# Schema.net
KiCad netlist of a schematic drawn in Altium Designer
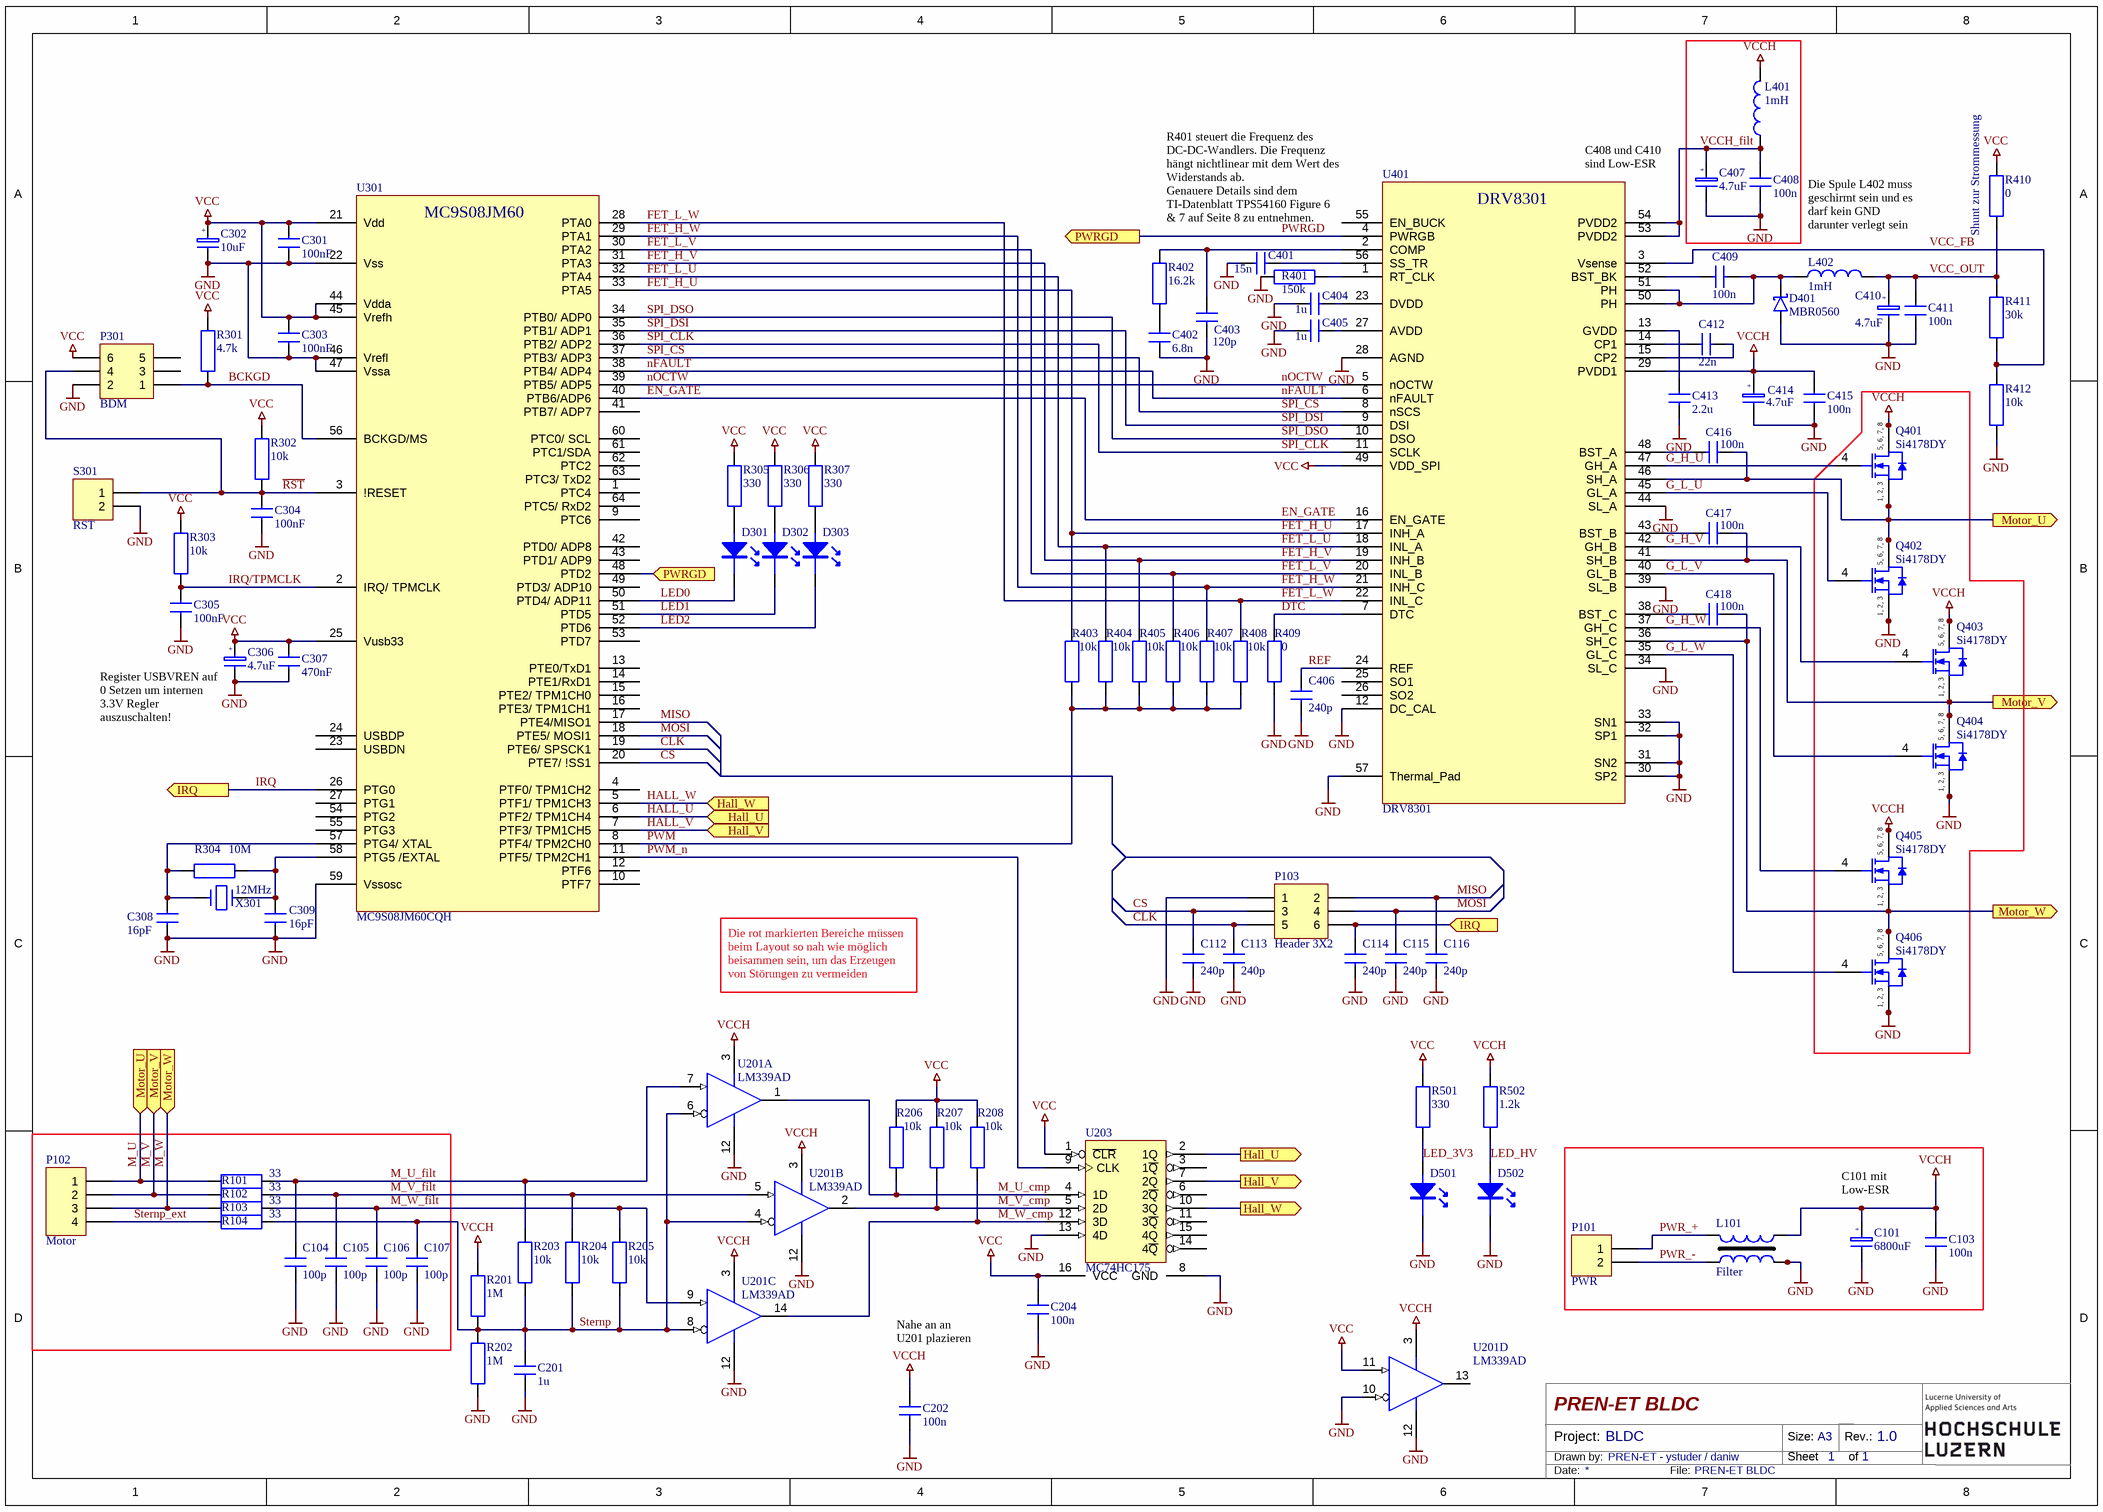
[diagram p0: Schema.SchDoc]

(export (version "E")
  (design (tool "Eeschema 10.0.6"))
  (components
    (comp (ref "C101")
      (value "6800uF")
      (footprint "CAPPA14.05-10.5x6.3")
      (description "Elektrolyt /polarisierter Kondensator")
      (libsource (lib "BLDC_Board_Library") (part "C? ELKO"))
    )
    (comp (ref "C103")
      (value "100n")
      (footprint "0805")
      (description "Normaler Kondensator")
      (libsource (lib "SPICE_HSLU") (part "C?"))
    )
    (comp (ref "C104")
      (value "100p")
      (footprint "0805")
      (description "Normaler Kondensator")
      (libsource (lib "SPICE_HSLU") (part "C?"))
    )
    (comp (ref "C105")
      (value "100p")
      (footprint "0805")
      (description "Normaler Kondensator")
      (libsource (lib "SPICE_HSLU") (part "C?"))
    )
    (comp (ref "C106")
      (value "100p")
      (footprint "0805")
      (description "Normaler Kondensator")
      (libsource (lib "SPICE_HSLU") (part "C?"))
    )
    (comp (ref "C107")
      (value "100p")
      (footprint "0805")
      (description "Normaler Kondensator")
      (libsource (lib "SPICE_HSLU") (part "C?"))
    )
    (comp (ref "C112")
      (value "240p")
      (footprint "0805")
      (description "Normaler Kondensator")
      (libsource (lib "SPICE_HSLU") (part "C?"))
    )
    (comp (ref "C113")
      (value "240p")
      (footprint "0805")
      (description "Normaler Kondensator")
      (libsource (lib "SPICE_HSLU") (part "C?"))
    )
    (comp (ref "C114")
      (value "240p")
      (footprint "0805")
      (description "Normaler Kondensator")
      (libsource (lib "SPICE_HSLU") (part "C?"))
    )
    (comp (ref "C115")
      (value "240p")
      (footprint "0805")
      (description "Normaler Kondensator")
      (libsource (lib "SPICE_HSLU") (part "C?"))
    )
    (comp (ref "C116")
      (value "240p")
      (footprint "0805")
      (description "Normaler Kondensator")
      (libsource (lib "SPICE_HSLU") (part "C?"))
    )
    (comp (ref "C201")
      (value "1u")
      (footprint "0805")
      (description "Normaler Kondensator")
      (libsource (lib "SPICE_HSLU") (part "C?"))
    )
    (comp (ref "C202")
      (value "100n")
      (footprint "0805")
      (description "Normaler Kondensator")
      (libsource (lib "SPICE_HSLU") (part "C?"))
    )
    (comp (ref "C204")
      (value "100n")
      (footprint "0805")
      (description "Normaler Kondensator")
      (libsource (lib "SPICE_HSLU") (part "C?"))
    )
    (comp (ref "C301")
      (value "100nF")
      (footprint "0805")
      (description "Normaler Kondensator")
      (libsource (lib "DEVICE_HSLU") (part "C?"))
    )
    (comp (ref "C302")
      (value "10uF")
      (footprint "1206")
      (description "Elektrolyt /polarisierter Kondensator")
      (libsource (lib "BLDC_Board_Library") (part "C? ELKO"))
    )
    (comp (ref "C303")
      (value "100nF")
      (footprint "0805")
      (description "Normaler Kondensator")
      (libsource (lib "DEVICE_HSLU") (part "C?"))
    )
    (comp (ref "C304")
      (value "100nF")
      (footprint "0805")
      (description "Normaler Kondensator")
      (libsource (lib "DEVICE_HSLU") (part "C?"))
    )
    (comp (ref "C305")
      (value "100nF")
      (footprint "0805")
      (description "Normaler Kondensator")
      (libsource (lib "DEVICE_HSLU") (part "C?"))
    )
    (comp (ref "C306")
      (value "4.7uF")
      (footprint "1206")
      (description "Elektrolyt /polarisierter Kondensator")
      (libsource (lib "BLDC_Board_Library") (part "C? ELKO"))
    )
    (comp (ref "C307")
      (value "470nF")
      (footprint "0805")
      (description "Normaler Kondensator")
      (libsource (lib "PREN_Demoboard") (part "C?"))
    )
    (comp (ref "C308")
      (value "16pF")
      (footprint "0805")
      (description "Normaler Kondensator")
      (libsource (lib "DEVICE_HSLU") (part "C?"))
    )
    (comp (ref "C309")
      (value "16pF")
      (footprint "0805")
      (description "Normaler Kondensator")
      (libsource (lib "DEVICE_HSLU") (part "C?"))
    )
    (comp (ref "C401")
      (value "15n")
      (footprint "0805")
      (description "Normaler Kondensator")
      (libsource (lib "SPICE_HSLU") (part "C?"))
    )
    (comp (ref "C402")
      (value "6.8n")
      (footprint "0805")
      (description "Normaler Kondensator")
      (libsource (lib "SPICE_HSLU") (part "C?"))
    )
    (comp (ref "C403")
      (value "120p")
      (footprint "0805")
      (description "Normaler Kondensator")
      (libsource (lib "SPICE_HSLU") (part "C?"))
    )
    (comp (ref "C404")
      (value "1u")
      (footprint "0805")
      (description "Normaler Kondensator")
      (libsource (lib "SPICE_HSLU") (part "C?"))
    )
    (comp (ref "C405")
      (value "1u")
      (footprint "0805")
      (description "Normaler Kondensator")
      (libsource (lib "SPICE_HSLU") (part "C?"))
    )
    (comp (ref "C406")
      (value "240p")
      (footprint "0805")
      (description "Normaler Kondensator")
      (libsource (lib "SPICE_HSLU") (part "C?"))
    )
    (comp (ref "C407")
      (value "4.7uF")
      (footprint "1206")
      (description "Elektrolyt /polarisierter Kondensator")
      (libsource (lib "BLDC_Board_Library") (part "C? ELKO"))
    )
    (comp (ref "C408")
      (value "100n")
      (footprint "0805")
      (description "Normaler Kondensator")
      (libsource (lib "SPICE_HSLU") (part "C?"))
    )
    (comp (ref "C409")
      (value "100n")
      (footprint "0805")
      (description "Normaler Kondensator")
      (libsource (lib "SPICE_HSLU") (part "C?"))
    )
    (comp (ref "C410")
      (value "4.7uF")
      (footprint "1206")
      (description "Elektrolyt /polarisierter Kondensator")
      (libsource (lib "BLDC_Board_Library") (part "C? ELKO"))
    )
    (comp (ref "C411")
      (value "100n")
      (footprint "0805")
      (description "Normaler Kondensator")
      (libsource (lib "SPICE_HSLU") (part "C?"))
    )
    (comp (ref "C412")
      (value "22n")
      (footprint "0805")
      (description "Normaler Kondensator")
      (libsource (lib "SPICE_HSLU") (part "C?"))
    )
    (comp (ref "C413")
      (value "2.2u")
      (footprint "0805")
      (description "Normaler Kondensator")
      (libsource (lib "SPICE_HSLU") (part "C?"))
    )
    (comp (ref "C414")
      (value "4.7uF")
      (footprint "1206")
      (description "Elektrolyt /polarisierter Kondensator")
      (libsource (lib "BLDC_Board_Library") (part "C? ELKO"))
    )
    (comp (ref "C415")
      (value "100n")
      (footprint "0805")
      (description "Normaler Kondensator")
      (libsource (lib "SPICE_HSLU") (part "C?"))
    )
    (comp (ref "C416")
      (value "100n")
      (footprint "0805")
      (description "Normaler Kondensator")
      (libsource (lib "SPICE_HSLU") (part "C?"))
    )
    (comp (ref "C417")
      (value "100n")
      (footprint "0805")
      (description "Normaler Kondensator")
      (libsource (lib "SPICE_HSLU") (part "C?"))
    )
    (comp (ref "C418")
      (value "100n")
      (footprint "0805")
      (description "Normaler Kondensator")
      (libsource (lib "SPICE_HSLU") (part "C?"))
    )
    (comp (ref "D301") (value "LED") (footprint "0805") (libsource (lib "BLDC_Board_Library") (part "LED")))
    (comp (ref "D302") (value "LED") (footprint "0805") (libsource (lib "BLDC_Board_Library") (part "LED")))
    (comp (ref "D303") (value "LED") (footprint "0805") (libsource (lib "BLDC_Board_Library") (part "LED")))
    (comp (ref "D401")
      (value "MBR0560")
      (footprint "SOD-123")
      (description "Schottky Diode")
      (libsource (lib "BLDC_Board_Library") (part "DiodeSchottky"))
    )
    (comp (ref "D501") (value "LED") (footprint "0805") (libsource (lib "BLDC_Board_Library") (part "LED")))
    (comp (ref "D502") (value "LED") (footprint "0805") (libsource (lib "BLDC_Board_Library") (part "LED")))
    (comp (ref "L101")
      (value "Filter")
      (footprint "BNX")
      (libsource (lib "BLDC_Board_Library") (part "CommonFilter"))
    )
    (comp (ref "L401")
      (value "1mH")
      (footprint "SRR6603")
      (description "SRR1005-122K")
      (libsource (lib "SPICE_HSLU") (part "L?"))
    )
    (comp (ref "L402")
      (value "1mH")
      (footprint "SRR6603")
      (description "SRR1005-122K")
      (libsource (lib "SPICE_HSLU") (part "L?"))
    )
    (comp (ref "P101")
      (value "PWR")
      (footprint "Stecker_1x2_200mil")
      (description "Header, 2-Pin")
      (fields (field (name "PUBLISHER") "Altium Limited"))
      (libsource (lib "BLDC_Board_Library") (part "Header 2"))
    )
    (comp (ref "P102")
      (value "Motor")
      (footprint "Stecker_1x4_200mil")
      (description "Header, 4-Pin")
      (fields (field (name "PUBLISHER") "Altium Limited"))
      (libsource (lib "BLDC_Board_Library") (part "Header 4"))
    )
    (comp (ref "P103")
      (value "Header 3X2")
      (footprint "HDR2X3")
      (description "Header, 3-Pin, Dual row")
      (fields (field (name "PUBLISHER") "Altium Limited"))
      (libsource (lib "Miscellaneous Connectors") (part "Header 3X2"))
    )
    (comp (ref "P301")
      (value "BDM")
      (footprint "HDR2X3")
      (description "Header, 3-Pin, Dual row")
      (libsource (lib "") (part "Header 3X2_1"))
    )
    (comp (ref "Q401")
      (value "Si4178DY")
      (footprint "SO-8_N")
      (description "N-Channel 30V (D-S)  Rated MOSFET")
      (fields (field (name "PUBLISHER") "Altium Limited"))
      (libsource (lib "Vishay Siliconix Discrete MOSFET") (part "SI4412DY"))
    )
    (comp (ref "Q402")
      (value "Si4178DY")
      (footprint "SO-8_N")
      (description "N-Channel 30V (D-S)  Rated MOSFET")
      (fields (field (name "PUBLISHER") "Altium Limited"))
      (libsource (lib "Vishay Siliconix Discrete MOSFET") (part "SI4412DY"))
    )
    (comp (ref "Q403")
      (value "Si4178DY")
      (footprint "SO-8_N")
      (description "N-Channel 30V (D-S)  Rated MOSFET")
      (fields (field (name "PUBLISHER") "Altium Limited"))
      (libsource (lib "Vishay Siliconix Discrete MOSFET") (part "SI4412DY"))
    )
    (comp (ref "Q404")
      (value "Si4178DY")
      (footprint "SO-8_N")
      (description "N-Channel 30V (D-S)  Rated MOSFET")
      (fields (field (name "PUBLISHER") "Altium Limited"))
      (libsource (lib "Vishay Siliconix Discrete MOSFET") (part "SI4412DY"))
    )
    (comp (ref "Q405")
      (value "Si4178DY")
      (footprint "SO-8_N")
      (description "N-Channel 30V (D-S)  Rated MOSFET")
      (fields (field (name "PUBLISHER") "Altium Limited"))
      (libsource (lib "Vishay Siliconix Discrete MOSFET") (part "SI4412DY"))
    )
    (comp (ref "Q406")
      (value "Si4178DY")
      (footprint "SO-8_N")
      (description "N-Channel 30V (D-S)  Rated MOSFET")
      (fields (field (name "PUBLISHER") "Altium Limited"))
      (libsource (lib "Vishay Siliconix Discrete MOSFET") (part "SI4412DY"))
    )
    (comp (ref "R101")
      (value "33")
      (footprint "0805")
      (description "Normaler Widerstand")
      (libsource (lib "SPICE_HSLU") (part "R?"))
    )
    (comp (ref "R102")
      (value "33")
      (footprint "0805")
      (description "Normaler Widerstand")
      (libsource (lib "SPICE_HSLU") (part "R?"))
    )
    (comp (ref "R103")
      (value "33")
      (footprint "0805")
      (description "Normaler Widerstand")
      (libsource (lib "SPICE_HSLU") (part "R?"))
    )
    (comp (ref "R104")
      (value "33")
      (footprint "0805")
      (description "Normaler Widerstand")
      (libsource (lib "SPICE_HSLU") (part "R?"))
    )
    (comp (ref "R201")
      (value "1M")
      (footprint "0805")
      (description "Normaler Widerstand")
      (libsource (lib "SPICE_HSLU") (part "R?"))
    )
    (comp (ref "R202")
      (value "1M")
      (footprint "0805")
      (description "Normaler Widerstand")
      (libsource (lib "SPICE_HSLU") (part "R?"))
    )
    (comp (ref "R203")
      (value "10k")
      (footprint "0805")
      (description "Normaler Widerstand")
      (libsource (lib "SPICE_HSLU") (part "R?"))
    )
    (comp (ref "R204")
      (value "10k")
      (footprint "0805")
      (description "Normaler Widerstand")
      (libsource (lib "SPICE_HSLU") (part "R?"))
    )
    (comp (ref "R205")
      (value "10k")
      (footprint "0805")
      (description "Normaler Widerstand")
      (libsource (lib "SPICE_HSLU") (part "R?"))
    )
    (comp (ref "R206")
      (value "10k")
      (footprint "0805")
      (description "Normaler Widerstand")
      (libsource (lib "SPICE_HSLU") (part "R?"))
    )
    (comp (ref "R207")
      (value "10k")
      (footprint "0805")
      (description "Normaler Widerstand")
      (libsource (lib "SPICE_HSLU") (part "R?"))
    )
    (comp (ref "R208")
      (value "10k")
      (footprint "0805")
      (description "Normaler Widerstand")
      (libsource (lib "SPICE_HSLU") (part "R?"))
    )
    (comp (ref "R301")
      (value "4.7k")
      (footprint "0805")
      (description "Normaler Widerstand")
      (libsource (lib "DEVICE_HSLU") (part "R?"))
    )
    (comp (ref "R302")
      (value "10k")
      (footprint "0805")
      (description "Normaler Widerstand")
      (libsource (lib "DEVICE_HSLU") (part "R?"))
    )
    (comp (ref "R303")
      (value "10k")
      (footprint "0805")
      (description "Normaler Widerstand")
      (libsource (lib "DEVICE_HSLU") (part "R?"))
    )
    (comp (ref "R304")
      (value "10M")
      (footprint "0805")
      (description "Normaler Widerstand")
      (libsource (lib "DEVICE_HSLU") (part "R?"))
    )
    (comp (ref "R305")
      (value "330")
      (footprint "0805")
      (description "Normaler Widerstand")
      (libsource (lib "SPICE_HSLU") (part "R?"))
    )
    (comp (ref "R306")
      (value "330")
      (footprint "0805")
      (description "Normaler Widerstand")
      (libsource (lib "SPICE_HSLU") (part "R?"))
    )
    (comp (ref "R307")
      (value "330")
      (footprint "0805")
      (description "Normaler Widerstand")
      (libsource (lib "SPICE_HSLU") (part "R?"))
    )
    (comp (ref "R401")
      (value "150k")
      (footprint "0805")
      (description "Normaler Widerstand")
      (libsource (lib "SPICE_HSLU") (part "R?"))
    )
    (comp (ref "R402")
      (value "16.2k")
      (footprint "0805")
      (description "Normaler Widerstand")
      (libsource (lib "SPICE_HSLU") (part "R?"))
    )
    (comp (ref "R403")
      (value "10k")
      (footprint "0805")
      (description "Normaler Widerstand")
      (libsource (lib "SPICE_HSLU") (part "R?"))
    )
    (comp (ref "R404")
      (value "10k")
      (footprint "0805")
      (description "Normaler Widerstand")
      (libsource (lib "SPICE_HSLU") (part "R?"))
    )
    (comp (ref "R405")
      (value "10k")
      (footprint "0805")
      (description "Normaler Widerstand")
      (libsource (lib "SPICE_HSLU") (part "R?"))
    )
    (comp (ref "R406")
      (value "10k")
      (footprint "0805")
      (description "Normaler Widerstand")
      (libsource (lib "SPICE_HSLU") (part "R?"))
    )
    (comp (ref "R407")
      (value "10k")
      (footprint "0805")
      (description "Normaler Widerstand")
      (libsource (lib "SPICE_HSLU") (part "R?"))
    )
    (comp (ref "R408")
      (value "10k")
      (footprint "0805")
      (description "Normaler Widerstand")
      (libsource (lib "SPICE_HSLU") (part "R?"))
    )
    (comp (ref "R409")
      (value "0")
      (footprint "0805")
      (description "Normaler Widerstand")
      (libsource (lib "SPICE_HSLU") (part "R?"))
    )
    (comp (ref "R410")
      (value "0")
      (footprint "0805")
      (description "Normaler Widerstand")
      (libsource (lib "SPICE_HSLU") (part "R?"))
    )
    (comp (ref "R411")
      (value "30k")
      (footprint "0805")
      (description "Normaler Widerstand")
      (libsource (lib "SPICE_HSLU") (part "R?"))
    )
    (comp (ref "R412")
      (value "10k")
      (footprint "0805")
      (description "Normaler Widerstand")
      (libsource (lib "SPICE_HSLU") (part "R?"))
    )
    (comp (ref "R501")
      (value "330")
      (footprint "0805")
      (description "Normaler Widerstand")
      (libsource (lib "SPICE_HSLU") (part "R?"))
    )
    (comp (ref "R502")
      (value "1.2k")
      (footprint "0805")
      (description "Normaler Widerstand")
      (libsource (lib "SPICE_HSLU") (part "R?"))
    )
    (comp (ref "S301")
      (value "RST")
      (footprint "HDR1X2")
      (description "Header, 2-Pin")
      (fields (field (name "PUBLISHER") "Altium Limited"))
      (libsource (lib "Miscellaneous Connectors") (part "Header 2"))
    )
    (comp (ref "U201")
      (value "LM339AD")
      (footprint "D014_L")
      (description "Quad Differential Comparator")
      (fields (field (name "PUBLISHER") "Altium Limited"))
      (libsource (lib "TI Analog Comparator") (part "LM339AD"))
    )
    (comp (ref "U203")
      (value "MC74HC175")
      (footprint "SO-16")
      (description "QUAD D-TYPE FF CR")
      (libsource (lib "Standardlogik") (part "MC74HC175"))
    )
    (comp (ref "U301")
      (value "MC9S08JM60CQH")
      (footprint "QFP64(14x14)")
      (description "MCU")
      (libsource (lib "PREN_Demoboard") (part "MC9S08JM60"))
    )
    (comp (ref "U401")
      (value "DRV8301")
      (footprint "HTSSOP56")
      (libsource (lib "BLDC_Board_Library") (part "DRV8301"))
    )
    (comp (ref "X301") (value "12MHz") (footprint "HC/49US") (libsource (lib "DEVICE_HSLU") (part "CRYSTAL")))
  )
  (nets
    (net (code "1") (name "/BCKGD") (class "Default")
      (node (ref "P301") (pin "1") (pinfunction "1_1") (pintype "passive"))
      (node (ref "R301") (pin "2") (pintype "passive"))
      (node (ref "U301") (pin "56") (pinfunction "BCKGD/MS_56") (pintype "passive"))
    )
    (net (code "2") (name "/CLK") (class "Default")
      (node (ref "C113") (pin "1") (pinfunction "1_1") (pintype "passive"))
      (node (ref "P103") (pin "5") (pinfunction "5_5") (pintype "passive"))
      (node (ref "U301") (pin "19") (pinfunction "PTE6/_SPSCK1_19") (pintype "passive"))
    )
    (net (code "3") (name "/CS") (class "Default")
      (node (ref "C112") (pin "1") (pinfunction "1_1") (pintype "passive"))
      (node (ref "P103") (pin "3") (pinfunction "3_3") (pintype "passive"))
      (node (ref "U301") (pin "20") (pinfunction "PTE7/_!SS1_20") (pintype "passive"))
    )
    (net (code "4") (name "/DTC") (class "Default")
      (node (ref "R409") (pin "2") (pintype "passive"))
      (node (ref "U401") (pin "7") (pinfunction "DTC_7") (pintype "passive"))
    )
    (net (code "5") (name "/EN_GATE") (class "Default")
      (node (ref "U301") (pin "40") (pinfunction "PTB6/ADP6_40") (pintype "passive"))
      (node (ref "U401") (pin "16") (pinfunction "EN_GATE_16") (pintype "passive"))
    )
    (net (code "6") (name "/FET_H_U") (class "Default")
      (node (ref "R403") (pin "2") (pintype "passive"))
      (node (ref "U301") (pin "33") (pinfunction "PTA5_33") (pintype "passive"))
      (node (ref "U401") (pin "17") (pinfunction "INH_A_17") (pintype "passive"))
    )
    (net (code "7") (name "/FET_H_V") (class "Default")
      (node (ref "R405") (pin "2") (pintype "passive"))
      (node (ref "U301") (pin "31") (pinfunction "PTA3_31") (pintype "passive"))
      (node (ref "U401") (pin "19") (pinfunction "INH_B_19") (pintype "passive"))
    )
    (net (code "8") (name "/FET_H_W") (class "Default")
      (node (ref "R407") (pin "2") (pintype "passive"))
      (node (ref "U301") (pin "29") (pinfunction "PTA1_29") (pintype "passive"))
      (node (ref "U401") (pin "21") (pinfunction "INH_C_21") (pintype "passive"))
    )
    (net (code "9") (name "/FET_L_U") (class "Default")
      (node (ref "R404") (pin "2") (pintype "passive"))
      (node (ref "U301") (pin "32") (pinfunction "PTA4_32") (pintype "passive"))
      (node (ref "U401") (pin "18") (pinfunction "INL_A_18") (pintype "passive"))
    )
    (net (code "10") (name "/FET_L_V") (class "Default")
      (node (ref "R406") (pin "2") (pintype "passive"))
      (node (ref "U301") (pin "30") (pinfunction "PTA2_30") (pintype "passive"))
      (node (ref "U401") (pin "20") (pinfunction "INL_B_20") (pintype "passive"))
    )
    (net (code "11") (name "/FET_L_W") (class "Default")
      (node (ref "R408") (pin "2") (pintype "passive"))
      (node (ref "U301") (pin "28") (pinfunction "PTA0_28") (pintype "passive"))
      (node (ref "U401") (pin "22") (pinfunction "INL_C_22") (pintype "passive"))
    )
    (net (code "12") (name "/G_H_U") (class "Default")
      (node (ref "Q401") (pin "4") (pinfunction "G_4") (pintype "passive"))
      (node (ref "U401") (pin "47") (pinfunction "GH_A_47") (pintype "passive"))
    )
    (net (code "13") (name "/G_H_V") (class "Default")
      (node (ref "Q403") (pin "4") (pinfunction "G_4") (pintype "passive"))
      (node (ref "U401") (pin "42") (pinfunction "GH_B_42") (pintype "passive"))
    )
    (net (code "14") (name "/G_H_W") (class "Default")
      (node (ref "Q405") (pin "4") (pinfunction "G_4") (pintype "passive"))
      (node (ref "U401") (pin "37") (pinfunction "GH_C_37") (pintype "passive"))
    )
    (net (code "15") (name "/G_L_U") (class "Default")
      (node (ref "Q402") (pin "4") (pinfunction "G_4") (pintype "passive"))
      (node (ref "U401") (pin "45") (pinfunction "GL_A_45") (pintype "passive"))
    )
    (net (code "16") (name "/G_L_V") (class "Default")
      (node (ref "Q404") (pin "4") (pinfunction "G_4") (pintype "passive"))
      (node (ref "U401") (pin "40") (pinfunction "GL_B_40") (pintype "passive"))
    )
    (net (code "17") (name "/G_L_W") (class "Default")
      (node (ref "Q406") (pin "4") (pinfunction "G_4") (pintype "passive"))
      (node (ref "U401") (pin "35") (pinfunction "GL_C_35") (pintype "passive"))
    )
    (net (code "18") (name "/HALL_U") (class "Default")
      (node (ref "U203") (pin "2") (pinfunction "1Q_2") (pintype "output"))
      (node (ref "U301") (pin "6") (pinfunction "PTF2/_TPM1CH4_6") (pintype "passive"))
    )
    (net (code "19") (name "/HALL_V") (class "Default")
      (node (ref "U203") (pin "7") (pinfunction "2Q_7") (pintype "output"))
      (node (ref "U301") (pin "7") (pinfunction "PTF3/_TPM1CH5_7") (pintype "passive"))
    )
    (net (code "20") (name "/HALL_W") (class "Default")
      (node (ref "U203") (pin "10") (pinfunction "3Q_10") (pintype "output"))
      (node (ref "U301") (pin "5") (pinfunction "PTF1/_TPM1CH3_5") (pintype "passive"))
    )
    (net (code "21") (name "/IRQ") (class "Default")
      (node (ref "C114") (pin "1") (pinfunction "1_1") (pintype "passive"))
      (node (ref "P103") (pin "6") (pinfunction "6_6") (pintype "passive"))
      (node (ref "U301") (pin "26") (pinfunction "PTG0_26") (pintype "passive"))
    )
    (net (code "22") (name "/IRQ{slash}TPMCLK") (class "Default")
      (node (ref "C305") (pin "1") (pinfunction "1_1") (pintype "passive"))
      (node (ref "R303") (pin "2") (pintype "passive"))
      (node (ref "U301") (pin "2") (pinfunction "IRQ/_TPMCLK_2") (pintype "passive"))
    )
    (net (code "23") (name "/LED0") (class "Default")
      (node (ref "D301") (pin "1") (pintype "passive"))
      (node (ref "U301") (pin "50") (pinfunction "PTD4/_ADP11_50") (pintype "passive"))
    )
    (net (code "24") (name "/LED1") (class "Default")
      (node (ref "D302") (pin "1") (pintype "passive"))
      (node (ref "U301") (pin "51") (pinfunction "PTD5_51") (pintype "passive"))
    )
    (net (code "25") (name "/LED2") (class "Default")
      (node (ref "D303") (pin "1") (pintype "passive"))
      (node (ref "U301") (pin "52") (pinfunction "PTD6_52") (pintype "passive"))
    )
    (net (code "26") (name "/LED_3V3") (class "Default")
      (node (ref "D501") (pin "2") (pintype "passive"))
      (node (ref "R501") (pin "1") (pintype "passive"))
    )
    (net (code "27") (name "/LED_HV") (class "Default")
      (node (ref "D502") (pin "2") (pintype "passive"))
      (node (ref "R502") (pin "1") (pintype "passive"))
    )
    (net (code "28") (name "/MISO") (class "Default")
      (node (ref "C116") (pin "1") (pinfunction "1_1") (pintype "passive"))
      (node (ref "P103") (pin "2") (pinfunction "2_2") (pintype "passive"))
      (node (ref "U301") (pin "17") (pinfunction "PTE4/MISO1_17") (pintype "passive"))
    )
    (net (code "29") (name "/MOSI") (class "Default")
      (node (ref "C115") (pin "1") (pinfunction "1_1") (pintype "passive"))
      (node (ref "P103") (pin "4") (pinfunction "4_4") (pintype "passive"))
      (node (ref "U301") (pin "18") (pinfunction "PTE5/_MOSI1_18") (pintype "passive"))
    )
    (net (code "30") (name "/M_U") (class "Default")
      (node (ref "C416") (pin "1") (pinfunction "1_1") (pintype "passive"))
      (node (ref "P102") (pin "1") (pinfunction "1_1") (pintype "passive"))
      (node (ref "Q401") (pin "1") (pinfunction "S_1") (pintype "passive"))
      (node (ref "Q401") (pin "2") (pinfunction "S_2") (pintype "passive"))
      (node (ref "Q401") (pin "3") (pinfunction "S_3") (pintype "passive"))
      (node (ref "Q402") (pin "5") (pinfunction "D_5") (pintype "passive"))
      (node (ref "Q402") (pin "6") (pinfunction "D_6") (pintype "passive"))
      (node (ref "Q402") (pin "7") (pinfunction "D_7") (pintype "passive"))
      (node (ref "Q402") (pin "8") (pinfunction "D_8") (pintype "passive"))
      (node (ref "R101") (pin "1") (pintype "passive"))
      (node (ref "U401") (pin "46") (pinfunction "SH_A_46") (pintype "passive"))
    )
    (net (code "31") (name "/M_U_cmp") (class "Default")
      (node (ref "R206") (pin "1") (pintype "passive"))
      (node (ref "U201") (pin "1") (pinfunction "OUT_1") (pintype "open_collector"))
      (node (ref "U203") (pin "4") (pinfunction "1D_4") (pintype "input"))
    )
    (net (code "32") (name "/M_U_filt") (class "Default")
      (node (ref "C104") (pin "1") (pinfunction "1_1") (pintype "passive"))
      (node (ref "R101") (pin "2") (pintype "passive"))
      (node (ref "R203") (pin "2") (pintype "passive"))
      (node (ref "U201") (pin "7") (pinfunction "IN+_7") (pintype "input"))
    )
    (net (code "33") (name "/M_V") (class "Default")
      (node (ref "C417") (pin "1") (pinfunction "1_1") (pintype "passive"))
      (node (ref "P102") (pin "2") (pinfunction "2_2") (pintype "passive"))
      (node (ref "Q403") (pin "1") (pinfunction "S_1") (pintype "passive"))
      (node (ref "Q403") (pin "2") (pinfunction "S_2") (pintype "passive"))
      (node (ref "Q403") (pin "3") (pinfunction "S_3") (pintype "passive"))
      (node (ref "Q404") (pin "5") (pinfunction "D_5") (pintype "passive"))
      (node (ref "Q404") (pin "6") (pinfunction "D_6") (pintype "passive"))
      (node (ref "Q404") (pin "7") (pinfunction "D_7") (pintype "passive"))
      (node (ref "Q404") (pin "8") (pinfunction "D_8") (pintype "passive"))
      (node (ref "R102") (pin "1") (pintype "passive"))
      (node (ref "U401") (pin "41") (pinfunction "SH_B_41") (pintype "passive"))
    )
    (net (code "34") (name "/M_V_cmp") (class "Default")
      (node (ref "R207") (pin "1") (pintype "passive"))
      (node (ref "U201") (pin "2") (pinfunction "OUT_2") (pintype "open_collector"))
      (node (ref "U203") (pin "5") (pinfunction "2D_5") (pintype "input"))
    )
    (net (code "35") (name "/M_V_filt") (class "Default")
      (node (ref "C105") (pin "1") (pinfunction "1_1") (pintype "passive"))
      (node (ref "R102") (pin "2") (pintype "passive"))
      (node (ref "R204") (pin "2") (pintype "passive"))
      (node (ref "U201") (pin "5") (pinfunction "IN+_5") (pintype "input"))
    )
    (net (code "36") (name "/M_W") (class "Default")
      (node (ref "C418") (pin "1") (pinfunction "1_1") (pintype "passive"))
      (node (ref "P102") (pin "3") (pinfunction "3_3") (pintype "passive"))
      (node (ref "Q405") (pin "1") (pinfunction "S_1") (pintype "passive"))
      (node (ref "Q405") (pin "2") (pinfunction "S_2") (pintype "passive"))
      (node (ref "Q405") (pin "3") (pinfunction "S_3") (pintype "passive"))
      (node (ref "Q406") (pin "5") (pinfunction "D_5") (pintype "passive"))
      (node (ref "Q406") (pin "6") (pinfunction "D_6") (pintype "passive"))
      (node (ref "Q406") (pin "7") (pinfunction "D_7") (pintype "passive"))
      (node (ref "Q406") (pin "8") (pinfunction "D_8") (pintype "passive"))
      (node (ref "R103") (pin "1") (pintype "passive"))
      (node (ref "U401") (pin "36") (pinfunction "SH_C_36") (pintype "passive"))
    )
    (net (code "37") (name "/M_W_cmp") (class "Default")
      (node (ref "R208") (pin "1") (pintype "passive"))
      (node (ref "U201") (pin "14") (pinfunction "OUT_14") (pintype "open_collector"))
      (node (ref "U203") (pin "12") (pinfunction "3D_12") (pintype "input"))
    )
    (net (code "38") (name "/M_W_filt") (class "Default")
      (node (ref "C106") (pin "1") (pinfunction "1_1") (pintype "passive"))
      (node (ref "R103") (pin "2") (pintype "passive"))
      (node (ref "R205") (pin "2") (pintype "passive"))
      (node (ref "U201") (pin "9") (pinfunction "IN+_9") (pintype "input"))
    )
    (net (code "39") (name "/PWM") (class "Default")
      (node (ref "R403") (pin "1") (pintype "passive"))
      (node (ref "R404") (pin "1") (pintype "passive"))
      (node (ref "R405") (pin "1") (pintype "passive"))
      (node (ref "R406") (pin "1") (pintype "passive"))
      (node (ref "R407") (pin "1") (pintype "passive"))
      (node (ref "R408") (pin "1") (pintype "passive"))
      (node (ref "U301") (pin "8") (pinfunction "PTF4/_TPM2CH0_8") (pintype "passive"))
    )
    (net (code "40") (name "/PWM_n") (class "Default")
      (node (ref "U203") (pin "9") (pinfunction "CLK_9") (pintype "input"))
      (node (ref "U301") (pin "11") (pinfunction "PTF5/_TPM2CH1_11") (pintype "passive"))
    )
    (net (code "41") (name "/PWRGD") (class "Default")
      (node (ref "U301") (pin "48") (pinfunction "PTD2_48") (pintype "passive"))
      (node (ref "U401") (pin "4") (pinfunction "PWRGB_4") (pintype "passive"))
    )
    (net (code "42") (name "/PWR_+") (class "Default")
      (node (ref "L101") (pin "1") (pinfunction "1_1") (pintype "passive"))
      (node (ref "P101") (pin "1") (pinfunction "1_1") (pintype "passive"))
    )
    (net (code "43") (name "/PWR_-") (class "Default")
      (node (ref "L101") (pin "2") (pinfunction "2_2") (pintype "passive"))
      (node (ref "P101") (pin "2") (pinfunction "2_2") (pintype "passive"))
    )
    (net (code "44") (name "/REF") (class "Default")
      (node (ref "C406") (pin "1") (pinfunction "1_1") (pintype "passive"))
      (node (ref "U401") (pin "24") (pinfunction "REF_24") (pintype "passive"))
    )
    (net (code "45") (name "/SPI_CLK") (class "Default")
      (node (ref "U301") (pin "36") (pinfunction "PTB2/_ADP2_36") (pintype "passive"))
      (node (ref "U401") (pin "11") (pinfunction "SCLK_11") (pintype "passive"))
    )
    (net (code "46") (name "/SPI_CS") (class "Default")
      (node (ref "U301") (pin "37") (pinfunction "PTB3/_ADP3_37") (pintype "passive"))
      (node (ref "U401") (pin "8") (pinfunction "nSCS_8") (pintype "passive"))
    )
    (net (code "47") (name "/SPI_DSI") (class "Default")
      (node (ref "U301") (pin "35") (pinfunction "PTB1/_ADP1_35") (pintype "passive"))
      (node (ref "U401") (pin "9") (pinfunction "DSI_9") (pintype "passive"))
    )
    (net (code "48") (name "/SPI_DSO") (class "Default")
      (node (ref "U301") (pin "34") (pinfunction "PTB0/_ADP0_34") (pintype "passive"))
      (node (ref "U401") (pin "10") (pinfunction "DSO_10") (pintype "passive"))
    )
    (net (code "49") (name "/Sternp") (class "Default")
      (node (ref "C107") (pin "1") (pinfunction "1_1") (pintype "passive"))
      (node (ref "C201") (pin "1") (pinfunction "1_1") (pintype "passive"))
      (node (ref "R104") (pin "2") (pintype "passive"))
      (node (ref "R201") (pin "1") (pintype "passive"))
      (node (ref "R202") (pin "2") (pintype "passive"))
      (node (ref "R203") (pin "1") (pintype "passive"))
      (node (ref "R204") (pin "1") (pintype "passive"))
      (node (ref "R205") (pin "1") (pintype "passive"))
      (node (ref "U201") (pin "4") (pinfunction "IN-_4") (pintype "input"))
      (node (ref "U201") (pin "6") (pinfunction "IN-_6") (pintype "input"))
      (node (ref "U201") (pin "8") (pinfunction "IN-_8") (pintype "input"))
    )
    (net (code "50") (name "/Sternp_ext") (class "Default")
      (node (ref "P102") (pin "4") (pinfunction "4_4") (pintype "passive"))
      (node (ref "R104") (pin "1") (pintype "passive"))
    )
    (net (code "51") (name "/VCCH_filt") (class "Default")
      (node (ref "C407") (pin "1") (pinfunction "1_1") (pintype "passive"))
      (node (ref "C408") (pin "1") (pinfunction "1_1") (pintype "passive"))
      (node (ref "L401") (pin "1") (pinfunction "1_1") (pintype "passive"))
      (node (ref "U401") (pin "53") (pinfunction "PVDD2_53") (pintype "passive"))
      (node (ref "U401") (pin "54") (pinfunction "PVDD2_54") (pintype "passive"))
    )
    (net (code "52") (name "/VCC_FB") (class "Default")
      (node (ref "R411") (pin "1") (pintype "passive"))
      (node (ref "R412") (pin "2") (pintype "passive"))
      (node (ref "U401") (pin "3") (pinfunction "Vsense_3") (pintype "passive"))
    )
    (net (code "53") (name "/VCC_OUT") (class "Default")
      (node (ref "C410") (pin "1") (pinfunction "1_1") (pintype "passive"))
      (node (ref "C411") (pin "1") (pinfunction "1_1") (pintype "passive"))
      (node (ref "L402") (pin "2") (pinfunction "2_2") (pintype "passive"))
      (node (ref "R410") (pin "2") (pintype "passive"))
      (node (ref "R411") (pin "2") (pintype "passive"))
    )
    (net (code "54") (name "/nFAULT") (class "Default")
      (node (ref "U301") (pin "38") (pinfunction "PTB4/_ADP4_38") (pintype "passive"))
      (node (ref "U401") (pin "6") (pinfunction "nFAULT_6") (pintype "passive"))
    )
    (net (code "55") (name "/nOCTW") (class "Default")
      (node (ref "U301") (pin "39") (pinfunction "PTB5/_ADP5_39") (pintype "passive"))
      (node (ref "U401") (pin "5") (pinfunction "nOCTW_5") (pintype "passive"))
    )
    (net (code "56") (name "/~{RST}") (class "Default")
      (node (ref "C304") (pin "1") (pinfunction "1_1") (pintype "passive"))
      (node (ref "P301") (pin "4") (pinfunction "4_4") (pintype "passive"))
      (node (ref "R302") (pin "2") (pintype "passive"))
      (node (ref "S301") (pin "1") (pinfunction "1_1") (pintype "passive"))
      (node (ref "U301") (pin "3") (pinfunction "!RESET_3") (pintype "passive"))
    )
    (net (code "57") (name "GND") (class "Default")
      (node (ref "C101") (pin "2") (pinfunction "2_2") (pintype "passive"))
      (node (ref "C103") (pin "2") (pinfunction "2_2") (pintype "passive"))
      (node (ref "C104") (pin "2") (pinfunction "2_2") (pintype "passive"))
      (node (ref "C105") (pin "2") (pinfunction "2_2") (pintype "passive"))
      (node (ref "C106") (pin "2") (pinfunction "2_2") (pintype "passive"))
      (node (ref "C107") (pin "2") (pinfunction "2_2") (pintype "passive"))
      (node (ref "C112") (pin "2") (pinfunction "2_2") (pintype "passive"))
      (node (ref "C113") (pin "2") (pinfunction "2_2") (pintype "passive"))
      (node (ref "C114") (pin "2") (pinfunction "2_2") (pintype "passive"))
      (node (ref "C115") (pin "2") (pinfunction "2_2") (pintype "passive"))
      (node (ref "C116") (pin "2") (pinfunction "2_2") (pintype "passive"))
      (node (ref "C201") (pin "2") (pinfunction "2_2") (pintype "passive"))
      (node (ref "C202") (pin "2") (pinfunction "2_2") (pintype "passive"))
      (node (ref "C204") (pin "2") (pinfunction "2_2") (pintype "passive"))
      (node (ref "C301") (pin "2") (pinfunction "2_2") (pintype "passive"))
      (node (ref "C302") (pin "2") (pinfunction "2_2") (pintype "passive"))
      (node (ref "C303") (pin "2") (pinfunction "2_2") (pintype "passive"))
      (node (ref "C304") (pin "2") (pinfunction "2_2") (pintype "passive"))
      (node (ref "C305") (pin "2") (pinfunction "2_2") (pintype "passive"))
      (node (ref "C306") (pin "2") (pinfunction "2_2") (pintype "passive"))
      (node (ref "C307") (pin "2") (pinfunction "2_2") (pintype "passive"))
      (node (ref "C308") (pin "1") (pinfunction "1_1") (pintype "passive"))
      (node (ref "C309") (pin "1") (pinfunction "1_1") (pintype "passive"))
      (node (ref "C401") (pin "1") (pinfunction "1_1") (pintype "passive"))
      (node (ref "C402") (pin "2") (pinfunction "2_2") (pintype "passive"))
      (node (ref "C403") (pin "2") (pinfunction "2_2") (pintype "passive"))
      (node (ref "C404") (pin "2") (pinfunction "2_2") (pintype "passive"))
      (node (ref "C405") (pin "2") (pinfunction "2_2") (pintype "passive"))
      (node (ref "C406") (pin "2") (pinfunction "2_2") (pintype "passive"))
      (node (ref "C407") (pin "2") (pinfunction "2_2") (pintype "passive"))
      (node (ref "C408") (pin "2") (pinfunction "2_2") (pintype "passive"))
      (node (ref "C410") (pin "2") (pinfunction "2_2") (pintype "passive"))
      (node (ref "C411") (pin "2") (pinfunction "2_2") (pintype "passive"))
      (node (ref "C413") (pin "2") (pinfunction "2_2") (pintype "passive"))
      (node (ref "C414") (pin "2") (pinfunction "2_2") (pintype "passive"))
      (node (ref "C415") (pin "1") (pinfunction "1_1") (pintype "passive"))
      (node (ref "D401") (pin "A") (pinfunction "A_A") (pintype "passive"))
      (node (ref "D501") (pin "1") (pintype "passive"))
      (node (ref "D502") (pin "1") (pintype "passive"))
      (node (ref "L101") (pin "3") (pinfunction "3_3") (pintype "passive"))
      (node (ref "L101") (pin "4") (pinfunction "4_4") (pintype "passive"))
      (node (ref "L101") (pin "6") (pinfunction "6_6") (pintype "passive"))
      (node (ref "P103") (pin "1") (pinfunction "1_1") (pintype "passive"))
      (node (ref "P301") (pin "2") (pinfunction "2_2") (pintype "passive"))
      (node (ref "Q402") (pin "1") (pinfunction "S_1") (pintype "passive"))
      (node (ref "Q402") (pin "2") (pinfunction "S_2") (pintype "passive"))
      (node (ref "Q402") (pin "3") (pinfunction "S_3") (pintype "passive"))
      (node (ref "Q404") (pin "1") (pinfunction "S_1") (pintype "passive"))
      (node (ref "Q404") (pin "2") (pinfunction "S_2") (pintype "passive"))
      (node (ref "Q404") (pin "3") (pinfunction "S_3") (pintype "passive"))
      (node (ref "Q406") (pin "1") (pinfunction "S_1") (pintype "passive"))
      (node (ref "Q406") (pin "2") (pinfunction "S_2") (pintype "passive"))
      (node (ref "Q406") (pin "3") (pinfunction "S_3") (pintype "passive"))
      (node (ref "R202") (pin "1") (pintype "passive"))
      (node (ref "R401") (pin "2") (pintype "passive"))
      (node (ref "R409") (pin "1") (pintype "passive"))
      (node (ref "R412") (pin "1") (pintype "passive"))
      (node (ref "S301") (pin "2") (pinfunction "2_2") (pintype "passive"))
      (node (ref "U201") (pin "10") (pinfunction "IN-_10") (pintype "input"))
      (node (ref "U201") (pin "12") (pinfunction "GND_12") (pintype "power_in"))
      (node (ref "U203") (pin "13") (pinfunction "4D_13") (pintype "input"))
      (node (ref "U203") (pin "8") (pinfunction "GND_8") (pintype "power_in"))
      (node (ref "U301") (pin "22") (pinfunction "Vss_22") (pintype "passive"))
      (node (ref "U301") (pin "46") (pinfunction "Vrefl_46") (pintype "passive"))
      (node (ref "U301") (pin "47") (pinfunction "Vssa_47") (pintype "passive"))
      (node (ref "U301") (pin "59") (pinfunction "Vssosc_59") (pintype "passive"))
      (node (ref "U401") (pin "12") (pinfunction "DC_CAL_12") (pintype "passive"))
      (node (ref "U401") (pin "28") (pinfunction "AGND_28") (pintype "passive"))
      (node (ref "U401") (pin "30") (pinfunction "SP2_30") (pintype "passive"))
      (node (ref "U401") (pin "31") (pinfunction "SN2_31") (pintype "passive"))
      (node (ref "U401") (pin "32") (pinfunction "SP1_32") (pintype "passive"))
      (node (ref "U401") (pin "33") (pinfunction "SN1_33") (pintype "passive"))
      (node (ref "U401") (pin "34") (pinfunction "SL_C_34") (pintype "passive"))
      (node (ref "U401") (pin "39") (pinfunction "SL_B_39") (pintype "passive"))
      (node (ref "U401") (pin "44") (pinfunction "SL_A_44") (pintype "passive"))
      (node (ref "U401") (pin "57") (pinfunction "Thermal_Pad_57") (pintype "passive"))
    )
    (net (code "58") (name "Net-(C402-Pad1)") (class "Default")
      (node (ref "C402") (pin "1") (pinfunction "1_1") (pintype "passive"))
      (node (ref "R402") (pin "1") (pintype "passive"))
    )
    (net (code "59") (name "Net-(C409-Pad1)") (class "Default")
      (node (ref "C409") (pin "1") (pinfunction "1_1") (pintype "passive"))
      (node (ref "D401") (pin "K") (pinfunction "K_K") (pintype "passive"))
      (node (ref "L402") (pin "1") (pinfunction "1_1") (pintype "passive"))
      (node (ref "U401") (pin "50") (pinfunction "PH_50") (pintype "passive"))
      (node (ref "U401") (pin "51") (pinfunction "PH_51") (pintype "passive"))
    )
    (net (code "60") (name "Net-(D301-Pad2)") (class "Default")
      (node (ref "D301") (pin "2") (pintype "passive"))
      (node (ref "R305") (pin "1") (pintype "passive"))
    )
    (net (code "61") (name "Net-(D302-Pad2)") (class "Default")
      (node (ref "D302") (pin "2") (pintype "passive"))
      (node (ref "R306") (pin "1") (pintype "passive"))
    )
    (net (code "62") (name "Net-(D303-Pad2)") (class "Default")
      (node (ref "D303") (pin "2") (pintype "passive"))
      (node (ref "R307") (pin "1") (pintype "passive"))
    )
    (net (code "63") (name "Net-(U301-PTG4{slash}_XTAL)") (class "Default")
      (node (ref "C308") (pin "2") (pinfunction "2_2") (pintype "passive"))
      (node (ref "R304") (pin "1") (pintype "passive"))
      (node (ref "U301") (pin "57") (pinfunction "PTG4/_XTAL_57") (pintype "passive"))
      (node (ref "X301") (pin "1") (pintype "passive"))
    )
    (net (code "64") (name "Net-(U301-PTG5_{slash}EXTAL)") (class "Default")
      (node (ref "C309") (pin "2") (pinfunction "2_2") (pintype "passive"))
      (node (ref "R304") (pin "2") (pintype "passive"))
      (node (ref "U301") (pin "58") (pinfunction "PTG5_/EXTAL_58") (pintype "passive"))
      (node (ref "X301") (pin "2") (pintype "passive"))
    )
    (net (code "65") (name "Net-(U401-AVDD)") (class "Default")
      (node (ref "C405") (pin "1") (pinfunction "1_1") (pintype "passive"))
      (node (ref "U401") (pin "27") (pinfunction "AVDD_27") (pintype "passive"))
    )
    (net (code "66") (name "Net-(U401-BST_A)") (class "Default")
      (node (ref "C416") (pin "2") (pinfunction "2_2") (pintype "passive"))
      (node (ref "U401") (pin "48") (pinfunction "BST_A_48") (pintype "passive"))
    )
    (net (code "67") (name "Net-(U401-BST_B)") (class "Default")
      (node (ref "C417") (pin "2") (pinfunction "2_2") (pintype "passive"))
      (node (ref "U401") (pin "43") (pinfunction "BST_B_43") (pintype "passive"))
    )
    (net (code "68") (name "Net-(U401-BST_BK)") (class "Default")
      (node (ref "C409") (pin "2") (pinfunction "2_2") (pintype "passive"))
      (node (ref "U401") (pin "52") (pinfunction "BST_BK_52") (pintype "passive"))
    )
    (net (code "69") (name "Net-(U401-BST_C)") (class "Default")
      (node (ref "C418") (pin "2") (pinfunction "2_2") (pintype "passive"))
      (node (ref "U401") (pin "38") (pinfunction "BST_C_38") (pintype "passive"))
    )
    (net (code "70") (name "Net-(U401-COMP)") (class "Default")
      (node (ref "C403") (pin "1") (pinfunction "1_1") (pintype "passive"))
      (node (ref "R402") (pin "2") (pintype "passive"))
      (node (ref "U401") (pin "2") (pinfunction "COMP_2") (pintype "passive"))
    )
    (net (code "71") (name "Net-(U401-CP1)") (class "Default")
      (node (ref "C412") (pin "2") (pinfunction "2_2") (pintype "passive"))
      (node (ref "U401") (pin "14") (pinfunction "CP1_14") (pintype "passive"))
    )
    (net (code "72") (name "Net-(U401-CP2)") (class "Default")
      (node (ref "C412") (pin "1") (pinfunction "1_1") (pintype "passive"))
      (node (ref "U401") (pin "15") (pinfunction "CP2_15") (pintype "passive"))
    )
    (net (code "73") (name "Net-(U401-DVDD)") (class "Default")
      (node (ref "C404") (pin "1") (pinfunction "1_1") (pintype "passive"))
      (node (ref "U401") (pin "23") (pinfunction "DVDD_23") (pintype "passive"))
    )
    (net (code "74") (name "Net-(U401-GVDD)") (class "Default")
      (node (ref "C413") (pin "1") (pinfunction "1_1") (pintype "passive"))
      (node (ref "U401") (pin "13") (pinfunction "GVDD_13") (pintype "passive"))
    )
    (net (code "75") (name "Net-(U401-RT_CLK)") (class "Default")
      (node (ref "R401") (pin "1") (pintype "passive"))
      (node (ref "U401") (pin "1") (pinfunction "RT_CLK_1") (pintype "passive"))
    )
    (net (code "76") (name "Net-(U401-SS_TR)") (class "Default")
      (node (ref "C401") (pin "2") (pinfunction "2_2") (pintype "passive"))
      (node (ref "U401") (pin "56") (pinfunction "SS_TR_56") (pintype "passive"))
    )
    (net (code "77") (name "VCC") (class "Default")
      (node (ref "C204") (pin "1") (pinfunction "1_1") (pintype "passive"))
      (node (ref "C301") (pin "1") (pinfunction "1_1") (pintype "passive"))
      (node (ref "C302") (pin "1") (pinfunction "1_1") (pintype "passive"))
      (node (ref "C303") (pin "1") (pinfunction "1_1") (pintype "passive"))
      (node (ref "C306") (pin "1") (pinfunction "1_1") (pintype "passive"))
      (node (ref "C307") (pin "1") (pinfunction "1_1") (pintype "passive"))
      (node (ref "P301") (pin "6") (pinfunction "6_6") (pintype "passive"))
      (node (ref "R206") (pin "2") (pintype "passive"))
      (node (ref "R207") (pin "2") (pintype "passive"))
      (node (ref "R208") (pin "2") (pintype "passive"))
      (node (ref "R301") (pin "1") (pintype "passive"))
      (node (ref "R302") (pin "1") (pintype "passive"))
      (node (ref "R303") (pin "1") (pintype "passive"))
      (node (ref "R305") (pin "2") (pintype "passive"))
      (node (ref "R306") (pin "2") (pintype "passive"))
      (node (ref "R307") (pin "2") (pintype "passive"))
      (node (ref "R410") (pin "1") (pintype "passive"))
      (node (ref "R501") (pin "2") (pintype "passive"))
      (node (ref "U201") (pin "11") (pinfunction "IN+_11") (pintype "input"))
      (node (ref "U203") (pin "1") (pinfunction "~{CLR}_1") (pintype "input"))
      (node (ref "U203") (pin "16") (pinfunction "VCC_16") (pintype "power_in"))
      (node (ref "U301") (pin "21") (pinfunction "Vdd_21") (pintype "passive"))
      (node (ref "U301") (pin "25") (pinfunction "Vusb33_25") (pintype "passive"))
      (node (ref "U301") (pin "44") (pinfunction "Vdda_44") (pintype "passive"))
      (node (ref "U301") (pin "45") (pinfunction "Vrefh_45") (pintype "passive"))
      (node (ref "U401") (pin "49") (pinfunction "VDD_SPI_49") (pintype "passive"))
    )
    (net (code "78") (name "VCCH") (class "Default")
      (node (ref "C101") (pin "1") (pinfunction "1_1") (pintype "passive"))
      (node (ref "C103") (pin "1") (pinfunction "1_1") (pintype "passive"))
      (node (ref "C202") (pin "1") (pinfunction "1_1") (pintype "passive"))
      (node (ref "C414") (pin "1") (pinfunction "1_1") (pintype "passive"))
      (node (ref "C415") (pin "2") (pinfunction "2_2") (pintype "passive"))
      (node (ref "L101") (pin "5") (pinfunction "5_5") (pintype "passive"))
      (node (ref "L401") (pin "2") (pinfunction "2_2") (pintype "passive"))
      (node (ref "Q401") (pin "5") (pinfunction "D_5") (pintype "passive"))
      (node (ref "Q401") (pin "6") (pinfunction "D_6") (pintype "passive"))
      (node (ref "Q401") (pin "7") (pinfunction "D_7") (pintype "passive"))
      (node (ref "Q401") (pin "8") (pinfunction "D_8") (pintype "passive"))
      (node (ref "Q403") (pin "5") (pinfunction "D_5") (pintype "passive"))
      (node (ref "Q403") (pin "6") (pinfunction "D_6") (pintype "passive"))
      (node (ref "Q403") (pin "7") (pinfunction "D_7") (pintype "passive"))
      (node (ref "Q403") (pin "8") (pinfunction "D_8") (pintype "passive"))
      (node (ref "Q405") (pin "5") (pinfunction "D_5") (pintype "passive"))
      (node (ref "Q405") (pin "6") (pinfunction "D_6") (pintype "passive"))
      (node (ref "Q405") (pin "7") (pinfunction "D_7") (pintype "passive"))
      (node (ref "Q405") (pin "8") (pinfunction "D_8") (pintype "passive"))
      (node (ref "R201") (pin "2") (pintype "passive"))
      (node (ref "R502") (pin "2") (pintype "passive"))
      (node (ref "U201") (pin "3") (pinfunction "VCC_3") (pintype "power_in"))
      (node (ref "U401") (pin "29") (pinfunction "PVDD1_29") (pintype "passive"))
    )
    (net (code "79") (name "unconnected-(P301-Pad3)") (class "Default")
      (node (ref "P301") (pin "3") (pinfunction "3_3") (pintype "passive"))
    )
    (net (code "80") (name "unconnected-(P301-Pad5)") (class "Default")
      (node (ref "P301") (pin "5") (pinfunction "5_5") (pintype "passive"))
    )
    (net (code "81") (name "unconnected-(U201D-OUT-Pad13)") (class "Default")
      (node (ref "U201") (pin "13") (pinfunction "OUT_13") (pintype "open_collector"))
    )
    (net (code "82") (name "unconnected-(U203-1~{Q}-Pad3)") (class "Default")
      (node (ref "U203") (pin "3") (pinfunction "1~{Q}_3") (pintype "output"))
    )
    (net (code "83") (name "unconnected-(U203-2~{Q}-Pad6)") (class "Default")
      (node (ref "U203") (pin "6") (pinfunction "2~{Q}_6") (pintype "output"))
    )
    (net (code "84") (name "unconnected-(U203-3~{Q}-Pad11)") (class "Default")
      (node (ref "U203") (pin "11") (pinfunction "3~{Q}_11") (pintype "output"))
    )
    (net (code "85") (name "unconnected-(U203-4Q-Pad15)") (class "Default")
      (node (ref "U203") (pin "15") (pinfunction "4Q_15") (pintype "output"))
    )
    (net (code "86") (name "unconnected-(U203-4~{Q}-Pad14)") (class "Default")
      (node (ref "U203") (pin "14") (pinfunction "4~{Q}_14") (pintype "output"))
    )
    (net (code "87") (name "unconnected-(U301-PTB7{slash}_ADP7-Pad41)") (class "Default")
      (node (ref "U301") (pin "41") (pinfunction "PTB7/_ADP7_41") (pintype "passive"))
    )
    (net (code "88") (name "unconnected-(U301-PTC0{slash}_SCL-Pad60)") (class "Default")
      (node (ref "U301") (pin "60") (pinfunction "PTC0/_SCL_60") (pintype "passive"))
    )
    (net (code "89") (name "unconnected-(U301-PTC1{slash}SDA-Pad61)") (class "Default")
      (node (ref "U301") (pin "61") (pinfunction "PTC1/SDA_61") (pintype "passive"))
    )
    (net (code "90") (name "unconnected-(U301-PTC2-Pad62)") (class "Default")
      (node (ref "U301") (pin "62") (pinfunction "PTC2_62") (pintype "passive"))
    )
    (net (code "91") (name "unconnected-(U301-PTC3{slash}_TxD2-Pad63)") (class "Default")
      (node (ref "U301") (pin "63") (pinfunction "PTC3/_TxD2_63") (pintype "passive"))
    )
    (net (code "92") (name "unconnected-(U301-PTC4-Pad1)") (class "Default")
      (node (ref "U301") (pin "1") (pinfunction "PTC4_1") (pintype "passive"))
    )
    (net (code "93") (name "unconnected-(U301-PTC5{slash}_RxD2-Pad64)") (class "Default")
      (node (ref "U301") (pin "64") (pinfunction "PTC5/_RxD2_64") (pintype "passive"))
    )
    (net (code "94") (name "unconnected-(U301-PTC6-Pad9)") (class "Default")
      (node (ref "U301") (pin "9") (pinfunction "PTC6_9") (pintype "passive"))
    )
    (net (code "95") (name "unconnected-(U301-PTD0{slash}_ADP8-Pad42)") (class "Default")
      (node (ref "U301") (pin "42") (pinfunction "PTD0/_ADP8_42") (pintype "passive"))
    )
    (net (code "96") (name "unconnected-(U301-PTD1{slash}_ADP9-Pad43)") (class "Default")
      (node (ref "U301") (pin "43") (pinfunction "PTD1/_ADP9_43") (pintype "passive"))
    )
    (net (code "97") (name "unconnected-(U301-PTD3{slash}_ADP10-Pad49)") (class "Default")
      (node (ref "U301") (pin "49") (pinfunction "PTD3/_ADP10_49") (pintype "passive"))
    )
    (net (code "98") (name "unconnected-(U301-PTD7-Pad53)") (class "Default")
      (node (ref "U301") (pin "53") (pinfunction "PTD7_53") (pintype "passive"))
    )
    (net (code "99") (name "unconnected-(U301-PTE0{slash}TxD1-Pad13)") (class "Default")
      (node (ref "U301") (pin "13") (pinfunction "PTE0/TxD1_13") (pintype "passive"))
    )
    (net (code "100") (name "unconnected-(U301-PTE1{slash}RxD1-Pad14)") (class "Default")
      (node (ref "U301") (pin "14") (pinfunction "PTE1/RxD1_14") (pintype "passive"))
    )
    (net (code "101") (name "unconnected-(U301-PTE2{slash}_TPM1CH0-Pad15)") (class "Default")
      (node (ref "U301") (pin "15") (pinfunction "PTE2/_TPM1CH0_15") (pintype "passive"))
    )
    (net (code "102") (name "unconnected-(U301-PTE3{slash}_TPM1CH1-Pad16)") (class "Default")
      (node (ref "U301") (pin "16") (pinfunction "PTE3/_TPM1CH1_16") (pintype "passive"))
    )
    (net (code "103") (name "unconnected-(U301-PTF0{slash}_TPM1CH2-Pad4)") (class "Default")
      (node (ref "U301") (pin "4") (pinfunction "PTF0/_TPM1CH2_4") (pintype "passive"))
    )
    (net (code "104") (name "unconnected-(U301-PTF6-Pad12)") (class "Default")
      (node (ref "U301") (pin "12") (pinfunction "PTF6_12") (pintype "passive"))
    )
    (net (code "105") (name "unconnected-(U301-PTF7-Pad10)") (class "Default")
      (node (ref "U301") (pin "10") (pinfunction "PTF7_10") (pintype "passive"))
    )
    (net (code "106") (name "unconnected-(U301-PTG1-Pad27)") (class "Default")
      (node (ref "U301") (pin "27") (pinfunction "PTG1_27") (pintype "passive"))
    )
    (net (code "107") (name "unconnected-(U301-PTG2-Pad54)") (class "Default")
      (node (ref "U301") (pin "54") (pinfunction "PTG2_54") (pintype "passive"))
    )
    (net (code "108") (name "unconnected-(U301-PTG3-Pad55)") (class "Default")
      (node (ref "U301") (pin "55") (pinfunction "PTG3_55") (pintype "passive"))
    )
    (net (code "109") (name "unconnected-(U301-USBDN-Pad23)") (class "Default")
      (node (ref "U301") (pin "23") (pinfunction "USBDN_23") (pintype "passive"))
    )
    (net (code "110") (name "unconnected-(U301-USBDP-Pad24)") (class "Default")
      (node (ref "U301") (pin "24") (pinfunction "USBDP_24") (pintype "passive"))
    )
    (net (code "111") (name "unconnected-(U401-EN_BUCK-Pad55)") (class "Default")
      (node (ref "U401") (pin "55") (pinfunction "EN_BUCK_55") (pintype "passive"))
    )
    (net (code "112") (name "unconnected-(U401-SO1-Pad25)") (class "Default")
      (node (ref "U401") (pin "25") (pinfunction "SO1_25") (pintype "passive"))
    )
    (net (code "113") (name "unconnected-(U401-SO2-Pad26)") (class "Default")
      (node (ref "U401") (pin "26") (pinfunction "SO2_26") (pintype "passive"))
    )
  )
)
